# MotherBoardMicrocontrollerPart.net
KiCad netlist of a schematic drawn in Altium Designer
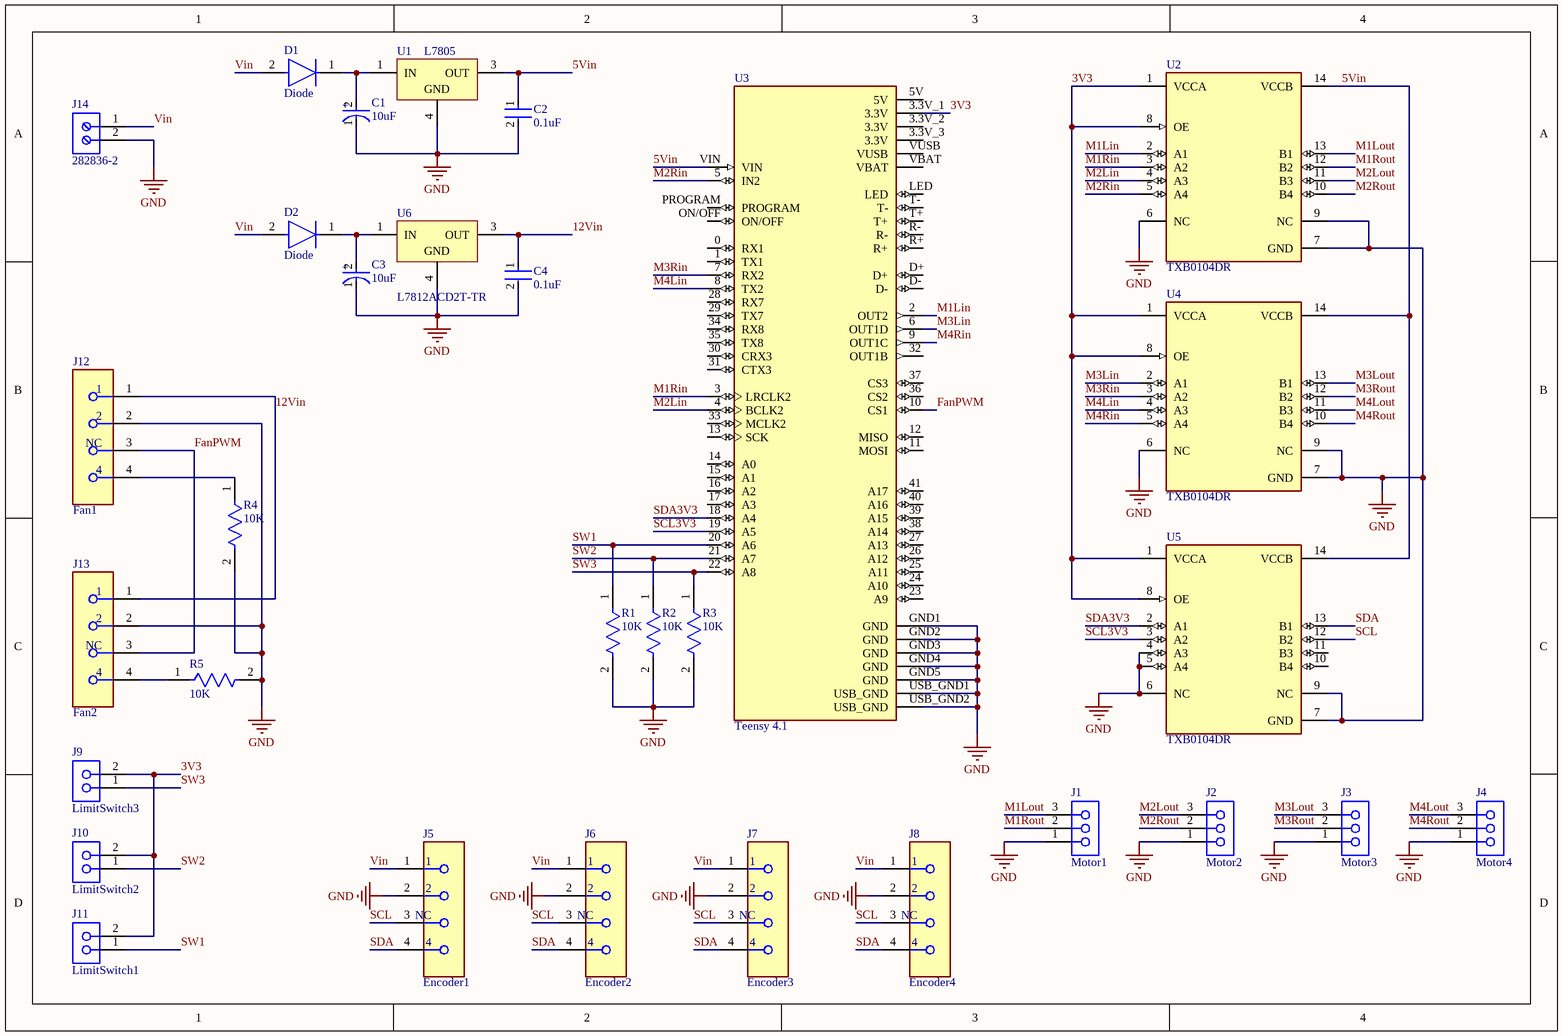
[diagram p0: MotherBoardMicrocontrollerPart.SchDoc]

(export (version "E")
  (design (tool "Eeschema 10.0.6"))
  (components
    (comp (ref "C1")
      (value "10uF")
      (footprint "FP-FKC-MFG")
      (description "CAP ALUM 10UF 20% 50V SMD")
      (fields (field (name "TOLERANCE") "20%") (field (name "VOLTAGE") "50V"))
      (libsource (lib "Altium Content Vault") (part "a00bbbee19879c290e62620ae7e47b1"))
    )
    (comp (ref "C2")
      (value "0.1uF")
      (footprint "FP-C322C104K5R5TA-MFG")
      (description "CAP CER 0.1UF 50V X7R RADIAL")
      (fields (field (name "TOLERANCE") "10%") (field (name "VOLTAGE") "50V"))
      (libsource (lib "Altium Content Vault") (part "b4654b650e69147ec39a6b967a45e02"))
    )
    (comp (ref "C3")
      (value "10uF")
      (footprint "FP-FKC-MFG")
      (description "CAP ALUM 10UF 20% 50V SMD")
      (fields (field (name "TOLERANCE") "20%") (field (name "VOLTAGE") "50V"))
      (libsource (lib "Altium Content Vault") (part "a00bbbee19879c290e62620ae7e47b1"))
    )
    (comp (ref "C4")
      (value "0.1uF")
      (footprint "FP-C322C104K5R5TA-MFG")
      (description "CAP CER 0.1UF 50V X7R RADIAL")
      (fields (field (name "TOLERANCE") "10%") (field (name "VOLTAGE") "50V"))
      (libsource (lib "Altium Content Vault") (part "b4654b650e69147ec39a6b967a45e02"))
    )
    (comp (ref "D1")
      (value "Diode")
      (footprint "FP-UF4007-MFG")
      (description "DIODE GEN PURP 1KV 1A DO204AL")
      (fields
        (field (name "MANUFACTURER") "Vishay")
        (field (name "OCTOPART") "https://octopart.com/uf4007-e3%2F54-vishay-42333894")
      )
      (libsource (lib "Altium Content Vault") (part "d7152d700b627762746794eb795d46e"))
    )
    (comp (ref "D2")
      (value "Diode")
      (footprint "FP-UF4007-MFG")
      (description "DIODE GEN PURP 1KV 1A DO204AL")
      (fields
        (field (name "MANUFACTURER") "Vishay")
        (field (name "OCTOPART") "https://octopart.com/uf4007-e3%2F54-vishay-42333894")
      )
      (libsource (lib "Altium Content Vault") (part "d7152d700b627762746794eb795d46e"))
    )
    (comp (ref "J1")
      (value "Motor1")
      (footprint "SMTC-BCS-103-X-S-TE")
      (description "Tiger Claw(TM) Pass-Through Socket, Vertical, -55 to 125 degC, 2.54 mm Pitch, 3-Pin, Female, RoHS")
      (fields (field (name "PARTNUMBER") "BCS-103-F-S-TE") (field (name "MANUFACTURER") "Samtec"))
      (libsource (lib "Altium Content Vault") (part "SMTC-BCS-103-X-S-TE"))
    )
    (comp (ref "J2")
      (value "Motor2")
      (footprint "SMTC-BCS-103-X-S-TE")
      (description "Tiger Claw(TM) Pass-Through Socket, Vertical, -55 to 125 degC, 2.54 mm Pitch, 3-Pin, Female, RoHS")
      (fields (field (name "PARTNUMBER") "BCS-103-F-S-TE") (field (name "MANUFACTURER") "Samtec"))
      (libsource (lib "Altium Content Vault") (part "SMTC-BCS-103-X-S-TE"))
    )
    (comp (ref "J3")
      (value "Motor3")
      (footprint "SMTC-BCS-103-X-S-TE")
      (description "Tiger Claw(TM) Pass-Through Socket, Vertical, -55 to 125 degC, 2.54 mm Pitch, 3-Pin, Female, RoHS")
      (fields (field (name "PARTNUMBER") "BCS-103-F-S-TE") (field (name "MANUFACTURER") "Samtec"))
      (libsource (lib "Altium Content Vault") (part "SMTC-BCS-103-X-S-TE"))
    )
    (comp (ref "J4")
      (value "Motor4")
      (footprint "SMTC-BCS-103-X-S-TE")
      (description "Tiger Claw(TM) Pass-Through Socket, Vertical, -55 to 125 degC, 2.54 mm Pitch, 3-Pin, Female, RoHS")
      (fields (field (name "PARTNUMBER") "BCS-103-F-S-TE") (field (name "MANUFACTURER") "Samtec"))
      (libsource (lib "Altium Content Vault") (part "SMTC-BCS-103-X-S-TE"))
    )
    (comp (ref "J5")
      (value "Encoder1")
      (footprint "FP-SSW-104-01-G-S-003-MFG")
      (description "CONN RCPT 4POS 0.1 GOLD PCB")
      (fields
        (field (name "OCTOPART") "https://octopart.com/ssw-104-01-g-s-003-samtec-17456976")
        (field (name "MANUFACTURER") "Samtec")
      )
      (libsource (lib "Altium Content Vault") (part "519380a8d8b67454a3edb3e4863aeb3"))
    )
    (comp (ref "J6")
      (value "Encoder2")
      (footprint "FP-SSW-104-01-G-S-003-MFG")
      (description "CONN RCPT 4POS 0.1 GOLD PCB")
      (fields
        (field (name "OCTOPART") "https://octopart.com/ssw-104-01-g-s-003-samtec-17456976")
        (field (name "MANUFACTURER") "Samtec")
      )
      (libsource (lib "Altium Content Vault") (part "519380a8d8b67454a3edb3e4863aeb3"))
    )
    (comp (ref "J7")
      (value "Encoder3")
      (footprint "FP-SSW-104-01-G-S-003-MFG")
      (description "CONN RCPT 4POS 0.1 GOLD PCB")
      (fields
        (field (name "OCTOPART") "https://octopart.com/ssw-104-01-g-s-003-samtec-17456976")
        (field (name "MANUFACTURER") "Samtec")
      )
      (libsource (lib "Altium Content Vault") (part "519380a8d8b67454a3edb3e4863aeb3"))
    )
    (comp (ref "J8")
      (value "Encoder4")
      (footprint "FP-SSW-104-01-G-S-003-MFG")
      (description "CONN RCPT 4POS 0.1 GOLD PCB")
      (fields
        (field (name "OCTOPART") "https://octopart.com/ssw-104-01-g-s-003-samtec-17456976")
        (field (name "MANUFACTURER") "Samtec")
      )
      (libsource (lib "Altium Content Vault") (part "519380a8d8b67454a3edb3e4863aeb3"))
    )
    (comp (ref "J9")
      (value "LimitSwitch3")
      (footprint "SMTC-SSW-102-02-X-S")
      (description "SQ Post Socket, Through-hole, Vertical, -55 to 105 degC, 2.54 mm Pitch, 2-Pin, Female, RoHS")
      (fields (field (name "MANUFACTURER") "Samtec") (field (name "PARTNUMBER") "SSW-102-02-T-S"))
      (libsource (lib "Altium Content Vault") (part "SMTC-SSW-102-02-X-S-X"))
    )
    (comp (ref "J10")
      (value "LimitSwitch2")
      (footprint "SMTC-SSW-102-02-X-S")
      (description "SQ Post Socket, Through-hole, Vertical, -55 to 105 degC, 2.54 mm Pitch, 2-Pin, Female, RoHS")
      (fields (field (name "MANUFACTURER") "Samtec") (field (name "PARTNUMBER") "SSW-102-02-T-S"))
      (libsource (lib "Altium Content Vault") (part "SMTC-SSW-102-02-X-S-X"))
    )
    (comp (ref "J11")
      (value "LimitSwitch1")
      (footprint "SMTC-SSW-102-02-X-S")
      (description "SQ Post Socket, Through-hole, Vertical, -55 to 105 degC, 2.54 mm Pitch, 2-Pin, Female, RoHS")
      (fields (field (name "MANUFACTURER") "Samtec") (field (name "PARTNUMBER") "SSW-102-02-T-S"))
      (libsource (lib "Altium Content Vault") (part "SMTC-SSW-102-02-X-S-X"))
    )
    (comp (ref "J12")
      (value "Fan1")
      (footprint "FP-SSW-104-01-G-S-003-MFG")
      (description "CONN RCPT 4POS 0.1 GOLD PCB")
      (fields
        (field (name "OCTOPART") "https://octopart.com/ssw-104-01-g-s-003-samtec-17456976")
        (field (name "MANUFACTURER") "Samtec")
      )
      (libsource (lib "") (part "519380a8d8b67454a3edb3e4863aeb3_1"))
    )
    (comp (ref "J13")
      (value "Fan2")
      (footprint "FP-SSW-104-01-G-S-003-MFG")
      (description "CONN RCPT 4POS 0.1 GOLD PCB")
      (fields
        (field (name "OCTOPART") "https://octopart.com/ssw-104-01-g-s-003-samtec-17456976")
        (field (name "MANUFACTURER") "Samtec")
      )
      (libsource (lib "") (part "519380a8d8b67454a3edb3e4863aeb3_1"))
    )
    (comp (ref "J14")
      (value "282836-2")
      (footprint "TECO-282836-2_V")
      (description "Female Header, Pitch 5 mm, 1 x 2 Position, Height 10 mm, Tail Length 3.5 mm, Rohs, Bulk")
      (fields (field (name "VOLTAGE") "300V") (field (name "MANUFACTURER") "TE Connectivity"))
      (libsource (lib "Altium Content Vault") (part "CN-1P-F-TB2"))
    )
    (comp (ref "R1")
      (value "10K")
      (footprint "FP-RC3216-IPC_C")
      (description "Res Thick Film 1206 10kΩ 5% 0.25W ±100ppm/°C Molded SMD T/R")
      (fields (field (name "TOLERANCE") "5%"))
      (libsource (lib "Altium Content Vault") (part "1029c3af85768c4190bb7ad29bc67b5"))
    )
    (comp (ref "R2")
      (value "10K")
      (footprint "FP-RC3216-IPC_C")
      (description "Res Thick Film 1206 10kΩ 5% 0.25W ±100ppm/°C Molded SMD T/R")
      (fields (field (name "TOLERANCE") "5%"))
      (libsource (lib "Altium Content Vault") (part "1029c3af85768c4190bb7ad29bc67b5"))
    )
    (comp (ref "R3")
      (value "10K")
      (footprint "FP-RC3216-IPC_C")
      (description "Res Thick Film 1206 10kΩ 5% 0.25W ±100ppm/°C Molded SMD T/R")
      (fields (field (name "TOLERANCE") "5%"))
      (libsource (lib "Altium Content Vault") (part "1029c3af85768c4190bb7ad29bc67b5"))
    )
    (comp (ref "R4")
      (value "10K")
      (footprint "FP-RC3216-IPC_C")
      (description "Res Thick Film 1206 10kΩ 5% 0.25W ±100ppm/°C Molded SMD T/R")
      (fields (field (name "TOLERANCE") "5%"))
      (libsource (lib "Altium Content Vault") (part "1029c3af85768c4190bb7ad29bc67b5"))
    )
    (comp (ref "R5")
      (value "10K")
      (footprint "FP-RC3216-IPC_C")
      (description "Res Thick Film 1206 10kΩ 5% 0.25W ±100ppm/°C Molded SMD T/R")
      (fields (field (name "TOLERANCE") "5%"))
      (libsource (lib "Altium Content Vault") (part "1029c3af85768c4190bb7ad29bc67b5"))
    )
    (comp (ref "U1")
      (value "L7805")
      (footprint "TO-263_M")
      (description "Positive Voltage Regulator, 3-Pin D2PAK, Tape and Reel")
      (libsource (lib "Altium Content Vault") (part "PM-REG-L4940-SOT3"))
    )
    (comp (ref "U2")
      (value "TXB0104DR")
      (footprint "FP-D0014A-MFG")
      (description "IC TRNSLTR BIDIRECTIONAL 14SOIC")
      (fields
        (field (name "OCTOPART") "https://octopart.com/txb0104dr-texas+instruments-5447502")
        (field (name "MANUFACTURER") "Texas Instruments")
      )
      (libsource (lib "Altium Content Vault") (part "30ede393f3855439dc6b40ac76d3203"))
    )
    (comp (ref "U3")
      (value "Teensy 4.1")
      (footprint "DEV-16771:MODULE_DEV-16771")
      (description "RT1062 Teensy 4.1 i.MX ARM Cortex-M7 MPU Embedded Evaluation Board")
      (fields (field (name "MP") "DEV-16771") (field (name "MF") "{'manufacturer': u'SparkFun Electronics'}"))
      (libsource (lib "*") (part "DEV-16771"))
    )
    (comp (ref "U4")
      (value "TXB0104DR")
      (footprint "FP-D0014A-MFG")
      (description "IC TRNSLTR BIDIRECTIONAL 14SOIC")
      (fields
        (field (name "OCTOPART") "https://octopart.com/txb0104dr-texas+instruments-5447502")
        (field (name "MANUFACTURER") "Texas Instruments")
      )
      (libsource (lib "Altium Content Vault") (part "30ede393f3855439dc6b40ac76d3203"))
    )
    (comp (ref "U5")
      (value "TXB0104DR")
      (footprint "FP-D0014A-MFG")
      (description "IC TRNSLTR BIDIRECTIONAL 14SOIC")
      (fields
        (field (name "OCTOPART") "https://octopart.com/txb0104dr-texas+instruments-5447502")
        (field (name "MANUFACTURER") "Texas Instruments")
      )
      (libsource (lib "Altium Content Vault") (part "30ede393f3855439dc6b40ac76d3203"))
    )
    (comp (ref "U6")
      (value "L7812ACD2T-TR")
      (footprint "TO-263_M")
      (description "Positive Voltage Regulator, 3-Pin D2PAK, Tape and Reel")
      (libsource (lib "Altium Content Vault") (part "PM-REG-L4940-SOT3"))
    )
  )
  (nets
    (net (code "1") (name "/3V3") (class "Default")
      (node (ref "J10") (pin "2") (pinfunction "2_2") (pintype "passive"))
      (node (ref "J11") (pin "2") (pinfunction "2_2") (pintype "passive"))
      (node (ref "J9") (pin "2") (pinfunction "2_2") (pintype "passive"))
      (node (ref "U2") (pin "1") (pinfunction "VCCA_1") (pintype "power_in"))
      (node (ref "U2") (pin "8") (pinfunction "OE_8") (pintype "input"))
      (node (ref "U3") (pin "3.3V_1") (pinfunction "3.3V_3.3V_1") (pintype "power_in"))
      (node (ref "U4") (pin "1") (pinfunction "VCCA_1") (pintype "power_in"))
      (node (ref "U4") (pin "8") (pinfunction "OE_8") (pintype "input"))
      (node (ref "U5") (pin "1") (pinfunction "VCCA_1") (pintype "power_in"))
      (node (ref "U5") (pin "8") (pinfunction "OE_8") (pintype "input"))
    )
    (net (code "2") (name "/5Vin") (class "Default")
      (node (ref "C2") (pin "1") (pinfunction "1_1") (pintype "passive"))
      (node (ref "U1") (pin "3") (pinfunction "OUT_3") (pintype "power_in"))
      (node (ref "U2") (pin "14") (pinfunction "VCCB_14") (pintype "power_in"))
      (node (ref "U3") (pin "VIN") (pinfunction "VIN_VIN") (pintype "input"))
      (node (ref "U4") (pin "14") (pinfunction "VCCB_14") (pintype "power_in"))
      (node (ref "U5") (pin "14") (pinfunction "VCCB_14") (pintype "power_in"))
    )
    (net (code "3") (name "/12Vin") (class "Default")
      (node (ref "C4") (pin "1") (pinfunction "1_1") (pintype "passive"))
      (node (ref "J12") (pin "1") (pinfunction "1_1") (pintype "passive"))
      (node (ref "J13") (pin "1") (pinfunction "1_1") (pintype "passive"))
      (node (ref "U6") (pin "3") (pinfunction "OUT_3") (pintype "power_in"))
    )
    (net (code "4") (name "/FanPWM") (class "Default")
      (node (ref "J12") (pin "3") (pinfunction "NC_3") (pintype "passive"))
      (node (ref "J13") (pin "3") (pinfunction "NC_3") (pintype "passive"))
      (node (ref "U3") (pin "10") (pinfunction "CS1_10") (pintype "bidirectional"))
    )
    (net (code "5") (name "/M1Lin") (class "Default")
      (node (ref "U2") (pin "2") (pinfunction "A1_2") (pintype "bidirectional"))
      (node (ref "U3") (pin "2") (pinfunction "OUT2_2") (pintype "output"))
    )
    (net (code "6") (name "/M1Lout") (class "Default")
      (node (ref "J1") (pin "3") (pinfunction "3_3") (pintype "passive"))
      (node (ref "U2") (pin "13") (pinfunction "B1_13") (pintype "bidirectional"))
    )
    (net (code "7") (name "/M1Rin") (class "Default")
      (node (ref "U2") (pin "3") (pinfunction "A2_3") (pintype "bidirectional"))
      (node (ref "U3") (pin "3") (pinfunction "LRCLK2_3") (pintype "bidirectional"))
    )
    (net (code "8") (name "/M1Rout") (class "Default")
      (node (ref "J1") (pin "2") (pinfunction "2_2") (pintype "passive"))
      (node (ref "U2") (pin "12") (pinfunction "B2_12") (pintype "bidirectional"))
    )
    (net (code "9") (name "/M2Lin") (class "Default")
      (node (ref "U2") (pin "4") (pinfunction "A3_4") (pintype "bidirectional"))
      (node (ref "U3") (pin "4") (pinfunction "BCLK2_4") (pintype "bidirectional"))
    )
    (net (code "10") (name "/M2Lout") (class "Default")
      (node (ref "J2") (pin "3") (pinfunction "3_3") (pintype "passive"))
      (node (ref "U2") (pin "11") (pinfunction "B3_11") (pintype "bidirectional"))
    )
    (net (code "11") (name "/M2Rin") (class "Default")
      (node (ref "U2") (pin "5") (pinfunction "A4_5") (pintype "bidirectional"))
      (node (ref "U3") (pin "5") (pinfunction "IN2_5") (pintype "bidirectional"))
    )
    (net (code "12") (name "/M2Rout") (class "Default")
      (node (ref "J2") (pin "2") (pinfunction "2_2") (pintype "passive"))
      (node (ref "U2") (pin "10") (pinfunction "B4_10") (pintype "bidirectional"))
    )
    (net (code "13") (name "/M3Lin") (class "Default")
      (node (ref "U3") (pin "6") (pinfunction "OUT1D_6") (pintype "output"))
      (node (ref "U4") (pin "2") (pinfunction "A1_2") (pintype "bidirectional"))
    )
    (net (code "14") (name "/M3Lout") (class "Default")
      (node (ref "J3") (pin "3") (pinfunction "3_3") (pintype "passive"))
      (node (ref "U4") (pin "13") (pinfunction "B1_13") (pintype "bidirectional"))
    )
    (net (code "15") (name "/M3Rin") (class "Default")
      (node (ref "U3") (pin "7") (pinfunction "RX2_7") (pintype "bidirectional"))
      (node (ref "U4") (pin "3") (pinfunction "A2_3") (pintype "bidirectional"))
    )
    (net (code "16") (name "/M3Rout") (class "Default")
      (node (ref "J3") (pin "2") (pinfunction "2_2") (pintype "passive"))
      (node (ref "U4") (pin "12") (pinfunction "B2_12") (pintype "bidirectional"))
    )
    (net (code "17") (name "/M4Lin") (class "Default")
      (node (ref "U3") (pin "8") (pinfunction "TX2_8") (pintype "bidirectional"))
      (node (ref "U4") (pin "4") (pinfunction "A3_4") (pintype "bidirectional"))
    )
    (net (code "18") (name "/M4Lout") (class "Default")
      (node (ref "J4") (pin "3") (pinfunction "3_3") (pintype "passive"))
      (node (ref "U4") (pin "11") (pinfunction "B3_11") (pintype "bidirectional"))
    )
    (net (code "19") (name "/M4Rin") (class "Default")
      (node (ref "U3") (pin "9") (pinfunction "OUT1C_9") (pintype "output"))
      (node (ref "U4") (pin "5") (pinfunction "A4_5") (pintype "bidirectional"))
    )
    (net (code "20") (name "/M4Rout") (class "Default")
      (node (ref "J4") (pin "2") (pinfunction "2_2") (pintype "passive"))
      (node (ref "U4") (pin "10") (pinfunction "B4_10") (pintype "bidirectional"))
    )
    (net (code "21") (name "/SCL") (class "Default")
      (node (ref "J5") (pin "3") (pinfunction "NC_3") (pintype "passive"))
      (node (ref "J6") (pin "3") (pinfunction "NC_3") (pintype "passive"))
      (node (ref "J7") (pin "3") (pinfunction "NC_3") (pintype "passive"))
      (node (ref "J8") (pin "3") (pinfunction "NC_3") (pintype "passive"))
      (node (ref "U5") (pin "12") (pinfunction "B2_12") (pintype "bidirectional"))
    )
    (net (code "22") (name "/SCL3V3") (class "Default")
      (node (ref "U3") (pin "19") (pinfunction "A5_19") (pintype "bidirectional"))
      (node (ref "U5") (pin "3") (pinfunction "A2_3") (pintype "bidirectional"))
    )
    (net (code "23") (name "/SDA") (class "Default")
      (node (ref "J5") (pin "4") (pinfunction "4_4") (pintype "passive"))
      (node (ref "J6") (pin "4") (pinfunction "4_4") (pintype "passive"))
      (node (ref "J7") (pin "4") (pinfunction "4_4") (pintype "passive"))
      (node (ref "J8") (pin "4") (pinfunction "4_4") (pintype "passive"))
      (node (ref "U5") (pin "13") (pinfunction "B1_13") (pintype "bidirectional"))
    )
    (net (code "24") (name "/SDA3V3") (class "Default")
      (node (ref "U3") (pin "18") (pinfunction "A4_18") (pintype "bidirectional"))
      (node (ref "U5") (pin "2") (pinfunction "A1_2") (pintype "bidirectional"))
    )
    (net (code "25") (name "/SW1") (class "Default")
      (node (ref "J11") (pin "1") (pinfunction "1_1") (pintype "passive"))
      (node (ref "R1") (pin "1") (pinfunction "1_1") (pintype "passive"))
      (node (ref "U3") (pin "20") (pinfunction "A6_20") (pintype "bidirectional"))
    )
    (net (code "26") (name "/SW2") (class "Default")
      (node (ref "J10") (pin "1") (pinfunction "1_1") (pintype "passive"))
      (node (ref "R2") (pin "1") (pinfunction "1_1") (pintype "passive"))
      (node (ref "U3") (pin "21") (pinfunction "A7_21") (pintype "bidirectional"))
    )
    (net (code "27") (name "/SW3") (class "Default")
      (node (ref "J9") (pin "1") (pinfunction "1_1") (pintype "passive"))
      (node (ref "R3") (pin "1") (pinfunction "1_1") (pintype "passive"))
      (node (ref "U3") (pin "22") (pinfunction "A8_22") (pintype "bidirectional"))
    )
    (net (code "28") (name "/Vin") (class "Default")
      (node (ref "D1") (pin "2") (pinfunction "A_2") (pintype "passive"))
      (node (ref "D2") (pin "2") (pinfunction "A_2") (pintype "passive"))
      (node (ref "J14") (pin "1") (pinfunction "1_1") (pintype "passive"))
      (node (ref "J5") (pin "1") (pinfunction "1_1") (pintype "passive"))
      (node (ref "J6") (pin "1") (pinfunction "1_1") (pintype "passive"))
      (node (ref "J7") (pin "1") (pinfunction "1_1") (pintype "passive"))
      (node (ref "J8") (pin "1") (pinfunction "1_1") (pintype "passive"))
    )
    (net (code "29") (name "GND") (class "Default")
      (node (ref "C1") (pin "1") (pinfunction "C_1") (pintype "passive"))
      (node (ref "C2") (pin "2") (pinfunction "2_2") (pintype "passive"))
      (node (ref "C3") (pin "1") (pinfunction "C_1") (pintype "passive"))
      (node (ref "C4") (pin "2") (pinfunction "2_2") (pintype "passive"))
      (node (ref "J1") (pin "1") (pinfunction "1_1") (pintype "passive"))
      (node (ref "J12") (pin "2") (pinfunction "2_2") (pintype "passive"))
      (node (ref "J13") (pin "2") (pinfunction "2_2") (pintype "passive"))
      (node (ref "J14") (pin "2") (pinfunction "2_2") (pintype "passive"))
      (node (ref "J2") (pin "1") (pinfunction "1_1") (pintype "passive"))
      (node (ref "J3") (pin "1") (pinfunction "1_1") (pintype "passive"))
      (node (ref "J4") (pin "1") (pinfunction "1_1") (pintype "passive"))
      (node (ref "J5") (pin "2") (pinfunction "2_2") (pintype "passive"))
      (node (ref "J6") (pin "2") (pinfunction "2_2") (pintype "passive"))
      (node (ref "J7") (pin "2") (pinfunction "2_2") (pintype "passive"))
      (node (ref "J8") (pin "2") (pinfunction "2_2") (pintype "passive"))
      (node (ref "R1") (pin "2") (pinfunction "2_2") (pintype "passive"))
      (node (ref "R2") (pin "2") (pinfunction "2_2") (pintype "passive"))
      (node (ref "R3") (pin "2") (pinfunction "2_2") (pintype "passive"))
      (node (ref "R4") (pin "2") (pinfunction "2_2") (pintype "passive"))
      (node (ref "R5") (pin "2") (pinfunction "2_2") (pintype "passive"))
      (node (ref "U1") (pin "4") (pinfunction "GND_4") (pintype "power_in"))
      (node (ref "U2") (pin "6") (pinfunction "NC_6") (pintype "passive"))
      (node (ref "U2") (pin "7") (pinfunction "GND_7") (pintype "power_in"))
      (node (ref "U2") (pin "9") (pinfunction "NC_9") (pintype "passive"))
      (node (ref "U3") (pin "GND1") (pinfunction "GND_GND1") (pintype "power_in"))
      (node (ref "U3") (pin "GND2") (pinfunction "GND_GND2") (pintype "power_in"))
      (node (ref "U3") (pin "GND3") (pinfunction "GND_GND3") (pintype "power_in"))
      (node (ref "U3") (pin "GND4") (pinfunction "GND_GND4") (pintype "power_in"))
      (node (ref "U3") (pin "GND5") (pinfunction "GND_GND5") (pintype "power_in"))
      (node (ref "U3") (pin "USB_GND1") (pinfunction "USB_GND_USB_GND1") (pintype "power_in"))
      (node (ref "U3") (pin "USB_GND2") (pinfunction "USB_GND_USB_GND2") (pintype "power_in"))
      (node (ref "U4") (pin "6") (pinfunction "NC_6") (pintype "passive"))
      (node (ref "U4") (pin "7") (pinfunction "GND_7") (pintype "power_in"))
      (node (ref "U4") (pin "9") (pinfunction "NC_9") (pintype "passive"))
      (node (ref "U5") (pin "4") (pinfunction "A3_4") (pintype "bidirectional"))
      (node (ref "U5") (pin "5") (pinfunction "A4_5") (pintype "bidirectional"))
      (node (ref "U5") (pin "6") (pinfunction "NC_6") (pintype "passive"))
      (node (ref "U5") (pin "7") (pinfunction "GND_7") (pintype "power_in"))
      (node (ref "U5") (pin "9") (pinfunction "NC_9") (pintype "passive"))
      (node (ref "U6") (pin "4") (pinfunction "GND_4") (pintype "power_in"))
    )
    (net (code "30") (name "Net-(C1-A)") (class "Default")
      (node (ref "C1") (pin "2") (pinfunction "A_2") (pintype "passive"))
      (node (ref "D1") (pin "1") (pinfunction "C_1") (pintype "passive"))
      (node (ref "U1") (pin "1") (pinfunction "IN_1") (pintype "power_in"))
    )
    (net (code "31") (name "Net-(C3-A)") (class "Default")
      (node (ref "C3") (pin "2") (pinfunction "A_2") (pintype "passive"))
      (node (ref "D2") (pin "1") (pinfunction "C_1") (pintype "passive"))
      (node (ref "U6") (pin "1") (pinfunction "IN_1") (pintype "power_in"))
    )
    (net (code "32") (name "Net-(J12-Pad4)") (class "Default")
      (node (ref "J12") (pin "4") (pinfunction "4_4") (pintype "passive"))
      (node (ref "R4") (pin "1") (pinfunction "1_1") (pintype "passive"))
    )
    (net (code "33") (name "Net-(J13-Pad4)") (class "Default")
      (node (ref "J13") (pin "4") (pinfunction "4_4") (pintype "passive"))
      (node (ref "R5") (pin "1") (pinfunction "1_1") (pintype "passive"))
    )
    (net (code "34") (name "unconnected-(U3-3.3V-Pad3.3V_2)") (class "Default")
      (node (ref "U3") (pin "3.3V_2") (pinfunction "3.3V_3.3V_2") (pintype "power_in"))
    )
    (net (code "35") (name "unconnected-(U3-3.3V-Pad3.3V_3)") (class "Default")
      (node (ref "U3") (pin "3.3V_3") (pinfunction "3.3V_3.3V_3") (pintype "power_in"))
    )
    (net (code "36") (name "unconnected-(U3-A0-Pad14)") (class "Default")
      (node (ref "U3") (pin "14") (pinfunction "A0_14") (pintype "bidirectional"))
    )
    (net (code "37") (name "unconnected-(U3-A1-Pad15)") (class "Default")
      (node (ref "U3") (pin "15") (pinfunction "A1_15") (pintype "bidirectional"))
    )
    (net (code "38") (name "unconnected-(U3-A2-Pad16)") (class "Default")
      (node (ref "U3") (pin "16") (pinfunction "A2_16") (pintype "bidirectional"))
    )
    (net (code "39") (name "unconnected-(U3-A3-Pad17)") (class "Default")
      (node (ref "U3") (pin "17") (pinfunction "A3_17") (pintype "bidirectional"))
    )
    (net (code "40") (name "unconnected-(U3-A9-Pad23)") (class "Default")
      (node (ref "U3") (pin "23") (pinfunction "A9_23") (pintype "bidirectional"))
    )
    (net (code "41") (name "unconnected-(U3-A10-Pad24)") (class "Default")
      (node (ref "U3") (pin "24") (pinfunction "A10_24") (pintype "bidirectional"))
    )
    (net (code "42") (name "unconnected-(U3-A11-Pad25)") (class "Default")
      (node (ref "U3") (pin "25") (pinfunction "A11_25") (pintype "bidirectional"))
    )
    (net (code "43") (name "unconnected-(U3-A12-Pad26)") (class "Default")
      (node (ref "U3") (pin "26") (pinfunction "A12_26") (pintype "bidirectional"))
    )
    (net (code "44") (name "unconnected-(U3-A13-Pad27)") (class "Default")
      (node (ref "U3") (pin "27") (pinfunction "A13_27") (pintype "bidirectional"))
    )
    (net (code "45") (name "unconnected-(U3-A14-Pad38)") (class "Default")
      (node (ref "U3") (pin "38") (pinfunction "A14_38") (pintype "bidirectional"))
    )
    (net (code "46") (name "unconnected-(U3-A15-Pad39)") (class "Default")
      (node (ref "U3") (pin "39") (pinfunction "A15_39") (pintype "bidirectional"))
    )
    (net (code "47") (name "unconnected-(U3-A16-Pad40)") (class "Default")
      (node (ref "U3") (pin "40") (pinfunction "A16_40") (pintype "bidirectional"))
    )
    (net (code "48") (name "unconnected-(U3-A17-Pad41)") (class "Default")
      (node (ref "U3") (pin "41") (pinfunction "A17_41") (pintype "bidirectional"))
    )
    (net (code "49") (name "unconnected-(U3-CRX3-Pad30)") (class "Default")
      (node (ref "U3") (pin "30") (pinfunction "CRX3_30") (pintype "bidirectional"))
    )
    (net (code "50") (name "unconnected-(U3-CS2-Pad36)") (class "Default")
      (node (ref "U3") (pin "36") (pinfunction "CS2_36") (pintype "bidirectional"))
    )
    (net (code "51") (name "unconnected-(U3-CS3-Pad37)") (class "Default")
      (node (ref "U3") (pin "37") (pinfunction "CS3_37") (pintype "bidirectional"))
    )
    (net (code "52") (name "unconnected-(U3-CTX3-Pad31)") (class "Default")
      (node (ref "U3") (pin "31") (pinfunction "CTX3_31") (pintype "bidirectional"))
    )
    (net (code "53") (name "unconnected-(U3-MCLK2-Pad33)") (class "Default")
      (node (ref "U3") (pin "33") (pinfunction "MCLK2_33") (pintype "bidirectional"))
    )
    (net (code "54") (name "unconnected-(U3-MISO-Pad12)") (class "Default")
      (node (ref "U3") (pin "12") (pinfunction "MISO_12") (pintype "bidirectional"))
    )
    (net (code "55") (name "unconnected-(U3-MOSI-Pad11)") (class "Default")
      (node (ref "U3") (pin "11") (pinfunction "MOSI_11") (pintype "bidirectional"))
    )
    (net (code "56") (name "unconnected-(U3-OUT1B-Pad32)") (class "Default")
      (node (ref "U3") (pin "32") (pinfunction "OUT1B_32") (pintype "output"))
    )
    (net (code "57") (name "unconnected-(U3-Pad5V)") (class "Default")
      (node (ref "U3") (pin "5V") (pinfunction "5V_5V") (pintype "power_in"))
    )
    (net (code "58") (name "unconnected-(U3-PadD+)") (class "Default")
      (node (ref "U3") (pin "D+") (pinfunction "D+_D+") (pintype "bidirectional"))
    )
    (net (code "59") (name "unconnected-(U3-PadD-)") (class "Default")
      (node (ref "U3") (pin "D-") (pinfunction "D-_D-") (pintype "bidirectional"))
    )
    (net (code "60") (name "unconnected-(U3-PadLED)") (class "Default")
      (node (ref "U3") (pin "LED") (pinfunction "LED_LED") (pintype "bidirectional"))
    )
    (net (code "61") (name "unconnected-(U3-PadON{slash}OFF)") (class "Default")
      (node (ref "U3") (pin "ON/OFF") (pinfunction "ON/OFF_ON/OFF") (pintype "bidirectional"))
    )
    (net (code "62") (name "unconnected-(U3-PadPROGRAM)") (class "Default")
      (node (ref "U3") (pin "PROGRAM") (pinfunction "PROGRAM_PROGRAM") (pintype "bidirectional"))
    )
    (net (code "63") (name "unconnected-(U3-PadR+)") (class "Default")
      (node (ref "U3") (pin "R+") (pinfunction "R+_R+") (pintype "bidirectional"))
    )
    (net (code "64") (name "unconnected-(U3-PadR-)") (class "Default")
      (node (ref "U3") (pin "R-") (pinfunction "R-_R-") (pintype "bidirectional"))
    )
    (net (code "65") (name "unconnected-(U3-PadT+)") (class "Default")
      (node (ref "U3") (pin "T+") (pinfunction "T+_T+") (pintype "bidirectional"))
    )
    (net (code "66") (name "unconnected-(U3-PadT-)") (class "Default")
      (node (ref "U3") (pin "T-") (pinfunction "T-_T-") (pintype "bidirectional"))
    )
    (net (code "67") (name "unconnected-(U3-PadVBAT)") (class "Default")
      (node (ref "U3") (pin "VBAT") (pinfunction "VBAT_VBAT") (pintype "passive"))
    )
    (net (code "68") (name "unconnected-(U3-PadVUSB)") (class "Default")
      (node (ref "U3") (pin "VUSB") (pinfunction "VUSB_VUSB") (pintype "passive"))
    )
    (net (code "69") (name "unconnected-(U3-RX1-Pad0)") (class "Default")
      (node (ref "U3") (pin "0") (pinfunction "RX1_0") (pintype "bidirectional"))
    )
    (net (code "70") (name "unconnected-(U3-RX7-Pad28)") (class "Default")
      (node (ref "U3") (pin "28") (pinfunction "RX7_28") (pintype "bidirectional"))
    )
    (net (code "71") (name "unconnected-(U3-RX8-Pad34)") (class "Default")
      (node (ref "U3") (pin "34") (pinfunction "RX8_34") (pintype "bidirectional"))
    )
    (net (code "72") (name "unconnected-(U3-SCK-Pad13)") (class "Default")
      (node (ref "U3") (pin "13") (pinfunction "SCK_13") (pintype "bidirectional"))
    )
    (net (code "73") (name "unconnected-(U3-TX1-Pad1)") (class "Default")
      (node (ref "U3") (pin "1") (pinfunction "TX1_1") (pintype "bidirectional"))
    )
    (net (code "74") (name "unconnected-(U3-TX7-Pad29)") (class "Default")
      (node (ref "U3") (pin "29") (pinfunction "TX7_29") (pintype "bidirectional"))
    )
    (net (code "75") (name "unconnected-(U3-TX8-Pad35)") (class "Default")
      (node (ref "U3") (pin "35") (pinfunction "TX8_35") (pintype "bidirectional"))
    )
    (net (code "76") (name "unconnected-(U5-B3-Pad11)") (class "Default")
      (node (ref "U5") (pin "11") (pinfunction "B3_11") (pintype "bidirectional"))
    )
    (net (code "77") (name "unconnected-(U5-B4-Pad10)") (class "Default")
      (node (ref "U5") (pin "10") (pinfunction "B4_10") (pintype "bidirectional"))
    )
  )
)
